# Connector.net
KiCad netlist of a schematic drawn in EAGLE
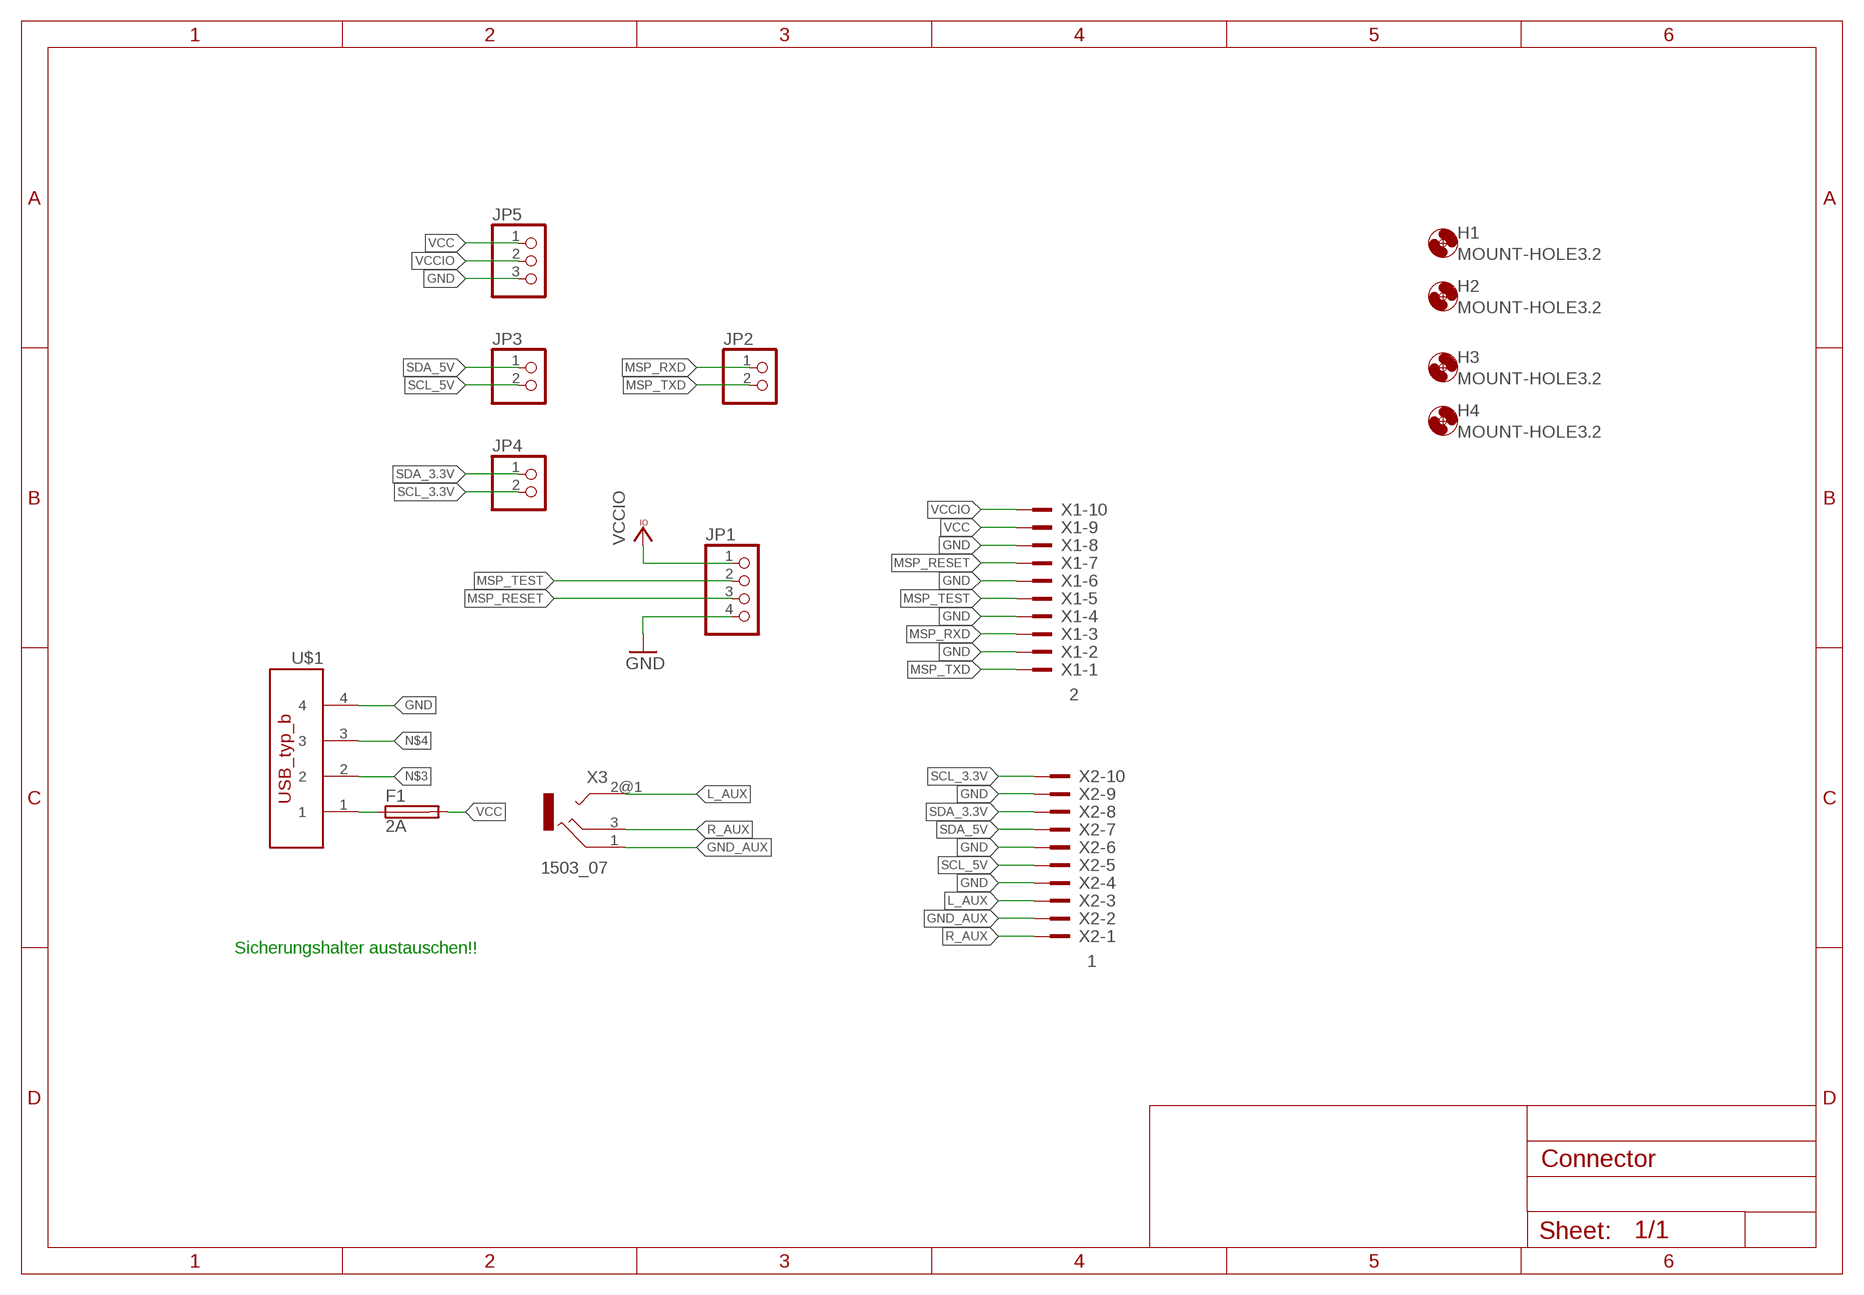
[diagram p0: schematic, sheet 1]

(export (version "E")
  (design (tool "Eeschema 10.0.6"))
  (components
    (comp (ref "F1")
      (value "2A")
      (footprint "eagle-import:SH22,5A")
      (fields (field (name "MPN") "0031.7701.11"))
      (libsource (lib "eagle-import") (part "SH22,5A"))
    )
    (comp (ref "H1")
      (value "MOUNT-HOLE3.2")
      (footprint "eagle-import:3,2")
      (libsource (lib "eagle-import") (part "MOUNT-HOLE3.2"))
    )
    (comp (ref "H2")
      (value "MOUNT-HOLE3.2")
      (footprint "eagle-import:3,2")
      (libsource (lib "eagle-import") (part "MOUNT-HOLE3.2"))
    )
    (comp (ref "H3")
      (value "MOUNT-HOLE3.2")
      (footprint "eagle-import:3,2")
      (libsource (lib "eagle-import") (part "MOUNT-HOLE3.2"))
    )
    (comp (ref "H4")
      (value "MOUNT-HOLE3.2")
      (footprint "eagle-import:3,2")
      (libsource (lib "eagle-import") (part "MOUNT-HOLE3.2"))
    )
    (comp (ref "JP1")
      (value "PINHD-1X4")
      (footprint "eagle-import:1X04")
      (libsource (lib "eagle-import") (part "PINHD-1X4"))
    )
    (comp (ref "JP2")
      (value "PINHD-1X2")
      (footprint "eagle-import:1X02")
      (libsource (lib "eagle-import") (part "PINHD-1X2"))
    )
    (comp (ref "JP3")
      (value "PINHD-1X2")
      (footprint "eagle-import:1X02")
      (libsource (lib "eagle-import") (part "PINHD-1X2"))
    )
    (comp (ref "JP4")
      (value "PINHD-1X2")
      (footprint "eagle-import:1X02")
      (libsource (lib "eagle-import") (part "PINHD-1X2"))
    )
    (comp (ref "JP5")
      (value "PINHD-1X3")
      (footprint "eagle-import:1X03")
      (libsource (lib "eagle-import") (part "PINHD-1X3"))
    )
    (comp (ref "U$1")
      (value "USB_TYP_B")
      (footprint "eagle-import:USB_TYP_B")
      (libsource (lib "eagle-import") (part "USB_TYP_B"))
    )
    (comp (ref "X1")
      (value "2")
      (footprint "eagle-import:PAK100_2500-10")
      (fields (field (name "MF") "3M") (field (name "MPN") "2510-6002UB"))
      (libsource (lib "eagle-import") (part "2510-"))
    )
    (comp (ref "X2")
      (value "1")
      (footprint "eagle-import:PAK100_2500-10")
      (fields (field (name "MF") "3M") (field (name "MPN") "2510-6002UB"))
      (libsource (lib "eagle-import") (part "2510-"))
    )
    (comp (ref "X3")
      (value "1503_07")
      (footprint "eagle-import:1503_07")
      (libsource (lib "eagle-import") (part "1503_?07"))
    )
  )
  (nets
    (net (code "1") (name "GND") (class "Default")
      (node (ref "JP1") (pin "4") (pinfunction "4_4") (pintype "passive"))
      (node (ref "JP5") (pin "3") (pinfunction "3_3") (pintype "passive"))
      (node (ref "U$1") (pin "4") (pinfunction "4_4") (pintype "bidirectional"))
      (node (ref "X1") (pin "2") (pinfunction "KL_2") (pintype "passive"))
      (node (ref "X1") (pin "4") (pinfunction "KL_4") (pintype "passive"))
      (node (ref "X1") (pin "6") (pinfunction "KL_6") (pintype "passive"))
      (node (ref "X1") (pin "8") (pinfunction "KL_8") (pintype "passive"))
      (node (ref "X2") (pin "4") (pinfunction "KL_4") (pintype "passive"))
      (node (ref "X2") (pin "6") (pinfunction "KL_6") (pintype "passive"))
      (node (ref "X2") (pin "9") (pinfunction "KL_9") (pintype "passive"))
    )
    (net (code "2") (name "GND_AUX") (class "Default")
      (node (ref "X2") (pin "2") (pinfunction "KL_2") (pintype "passive"))
      (node (ref "X3") (pin "1") (pinfunction "1_1") (pintype "passive"))
    )
    (net (code "3") (name "L_AUX") (class "Default")
      (node (ref "X2") (pin "3") (pinfunction "KL_3") (pintype "passive"))
      (node (ref "X3") (pin "2@1") (pinfunction "2_2@1") (pintype "passive"))
    )
    (net (code "4") (name "MSP_RESET") (class "Default")
      (node (ref "JP1") (pin "3") (pinfunction "3_3") (pintype "passive"))
      (node (ref "X1") (pin "7") (pinfunction "KL_7") (pintype "passive"))
    )
    (net (code "5") (name "MSP_RXD") (class "Default")
      (node (ref "JP2") (pin "1") (pinfunction "1_1") (pintype "passive"))
      (node (ref "X1") (pin "3") (pinfunction "KL_3") (pintype "passive"))
    )
    (net (code "6") (name "MSP_TEST") (class "Default")
      (node (ref "JP1") (pin "2") (pinfunction "2_2") (pintype "passive"))
      (node (ref "X1") (pin "5") (pinfunction "KL_5") (pintype "passive"))
    )
    (net (code "7") (name "MSP_TXD") (class "Default")
      (node (ref "JP2") (pin "2") (pinfunction "2_2") (pintype "passive"))
      (node (ref "X1") (pin "1") (pinfunction "KL_1") (pintype "passive"))
    )
    (net (code "8") (name "N$3") (class "Default")
      (node (ref "U$1") (pin "2") (pinfunction "2_2") (pintype "bidirectional"))
    )
    (net (code "9") (name "N$4") (class "Default")
      (node (ref "U$1") (pin "3") (pinfunction "3_3") (pintype "bidirectional"))
    )
    (net (code "10") (name "Net-(F1-Pad1)") (class "Default")
      (node (ref "F1") (pin "1") (pinfunction "1_1") (pintype "passive"))
      (node (ref "U$1") (pin "1") (pinfunction "1_1") (pintype "bidirectional"))
    )
    (net (code "11") (name "R_AUX") (class "Default")
      (node (ref "X2") (pin "1") (pinfunction "KL_1") (pintype "passive"))
      (node (ref "X3") (pin "3") (pinfunction "3_3") (pintype "passive"))
    )
    (net (code "12") (name "SCL_3.3V") (class "Default")
      (node (ref "JP4") (pin "2") (pinfunction "2_2") (pintype "passive"))
      (node (ref "X2") (pin "10") (pinfunction "KL_10") (pintype "passive"))
    )
    (net (code "13") (name "SCL_5V") (class "Default")
      (node (ref "JP3") (pin "2") (pinfunction "2_2") (pintype "passive"))
      (node (ref "X2") (pin "5") (pinfunction "KL_5") (pintype "passive"))
    )
    (net (code "14") (name "SDA_3.3V") (class "Default")
      (node (ref "JP4") (pin "1") (pinfunction "1_1") (pintype "passive"))
      (node (ref "X2") (pin "8") (pinfunction "KL_8") (pintype "passive"))
    )
    (net (code "15") (name "SDA_5V") (class "Default")
      (node (ref "JP3") (pin "1") (pinfunction "1_1") (pintype "passive"))
      (node (ref "X2") (pin "7") (pinfunction "KL_7") (pintype "passive"))
    )
    (net (code "16") (name "VCC") (class "Default")
      (node (ref "F1") (pin "2") (pinfunction "2_2") (pintype "passive"))
      (node (ref "JP5") (pin "1") (pinfunction "1_1") (pintype "passive"))
      (node (ref "X1") (pin "9") (pinfunction "KL_9") (pintype "passive"))
    )
    (net (code "17") (name "VCCIO") (class "Default")
      (node (ref "JP1") (pin "1") (pinfunction "1_1") (pintype "passive"))
      (node (ref "JP5") (pin "2") (pinfunction "2_2") (pintype "passive"))
      (node (ref "X1") (pin "10") (pinfunction "KL_10") (pintype "passive"))
    )
    (net (code "18") (name "unconnected-(X3-2-Pad2@2)") (class "Default")
      (node (ref "X3") (pin "2@2") (pinfunction "2_2@2") (pintype "passive"))
    )
  )
)
